# SCH_Teensy-PWM-Machine_2025-12-31.net
KiCad netlist of a schematic drawn in EasyEDA
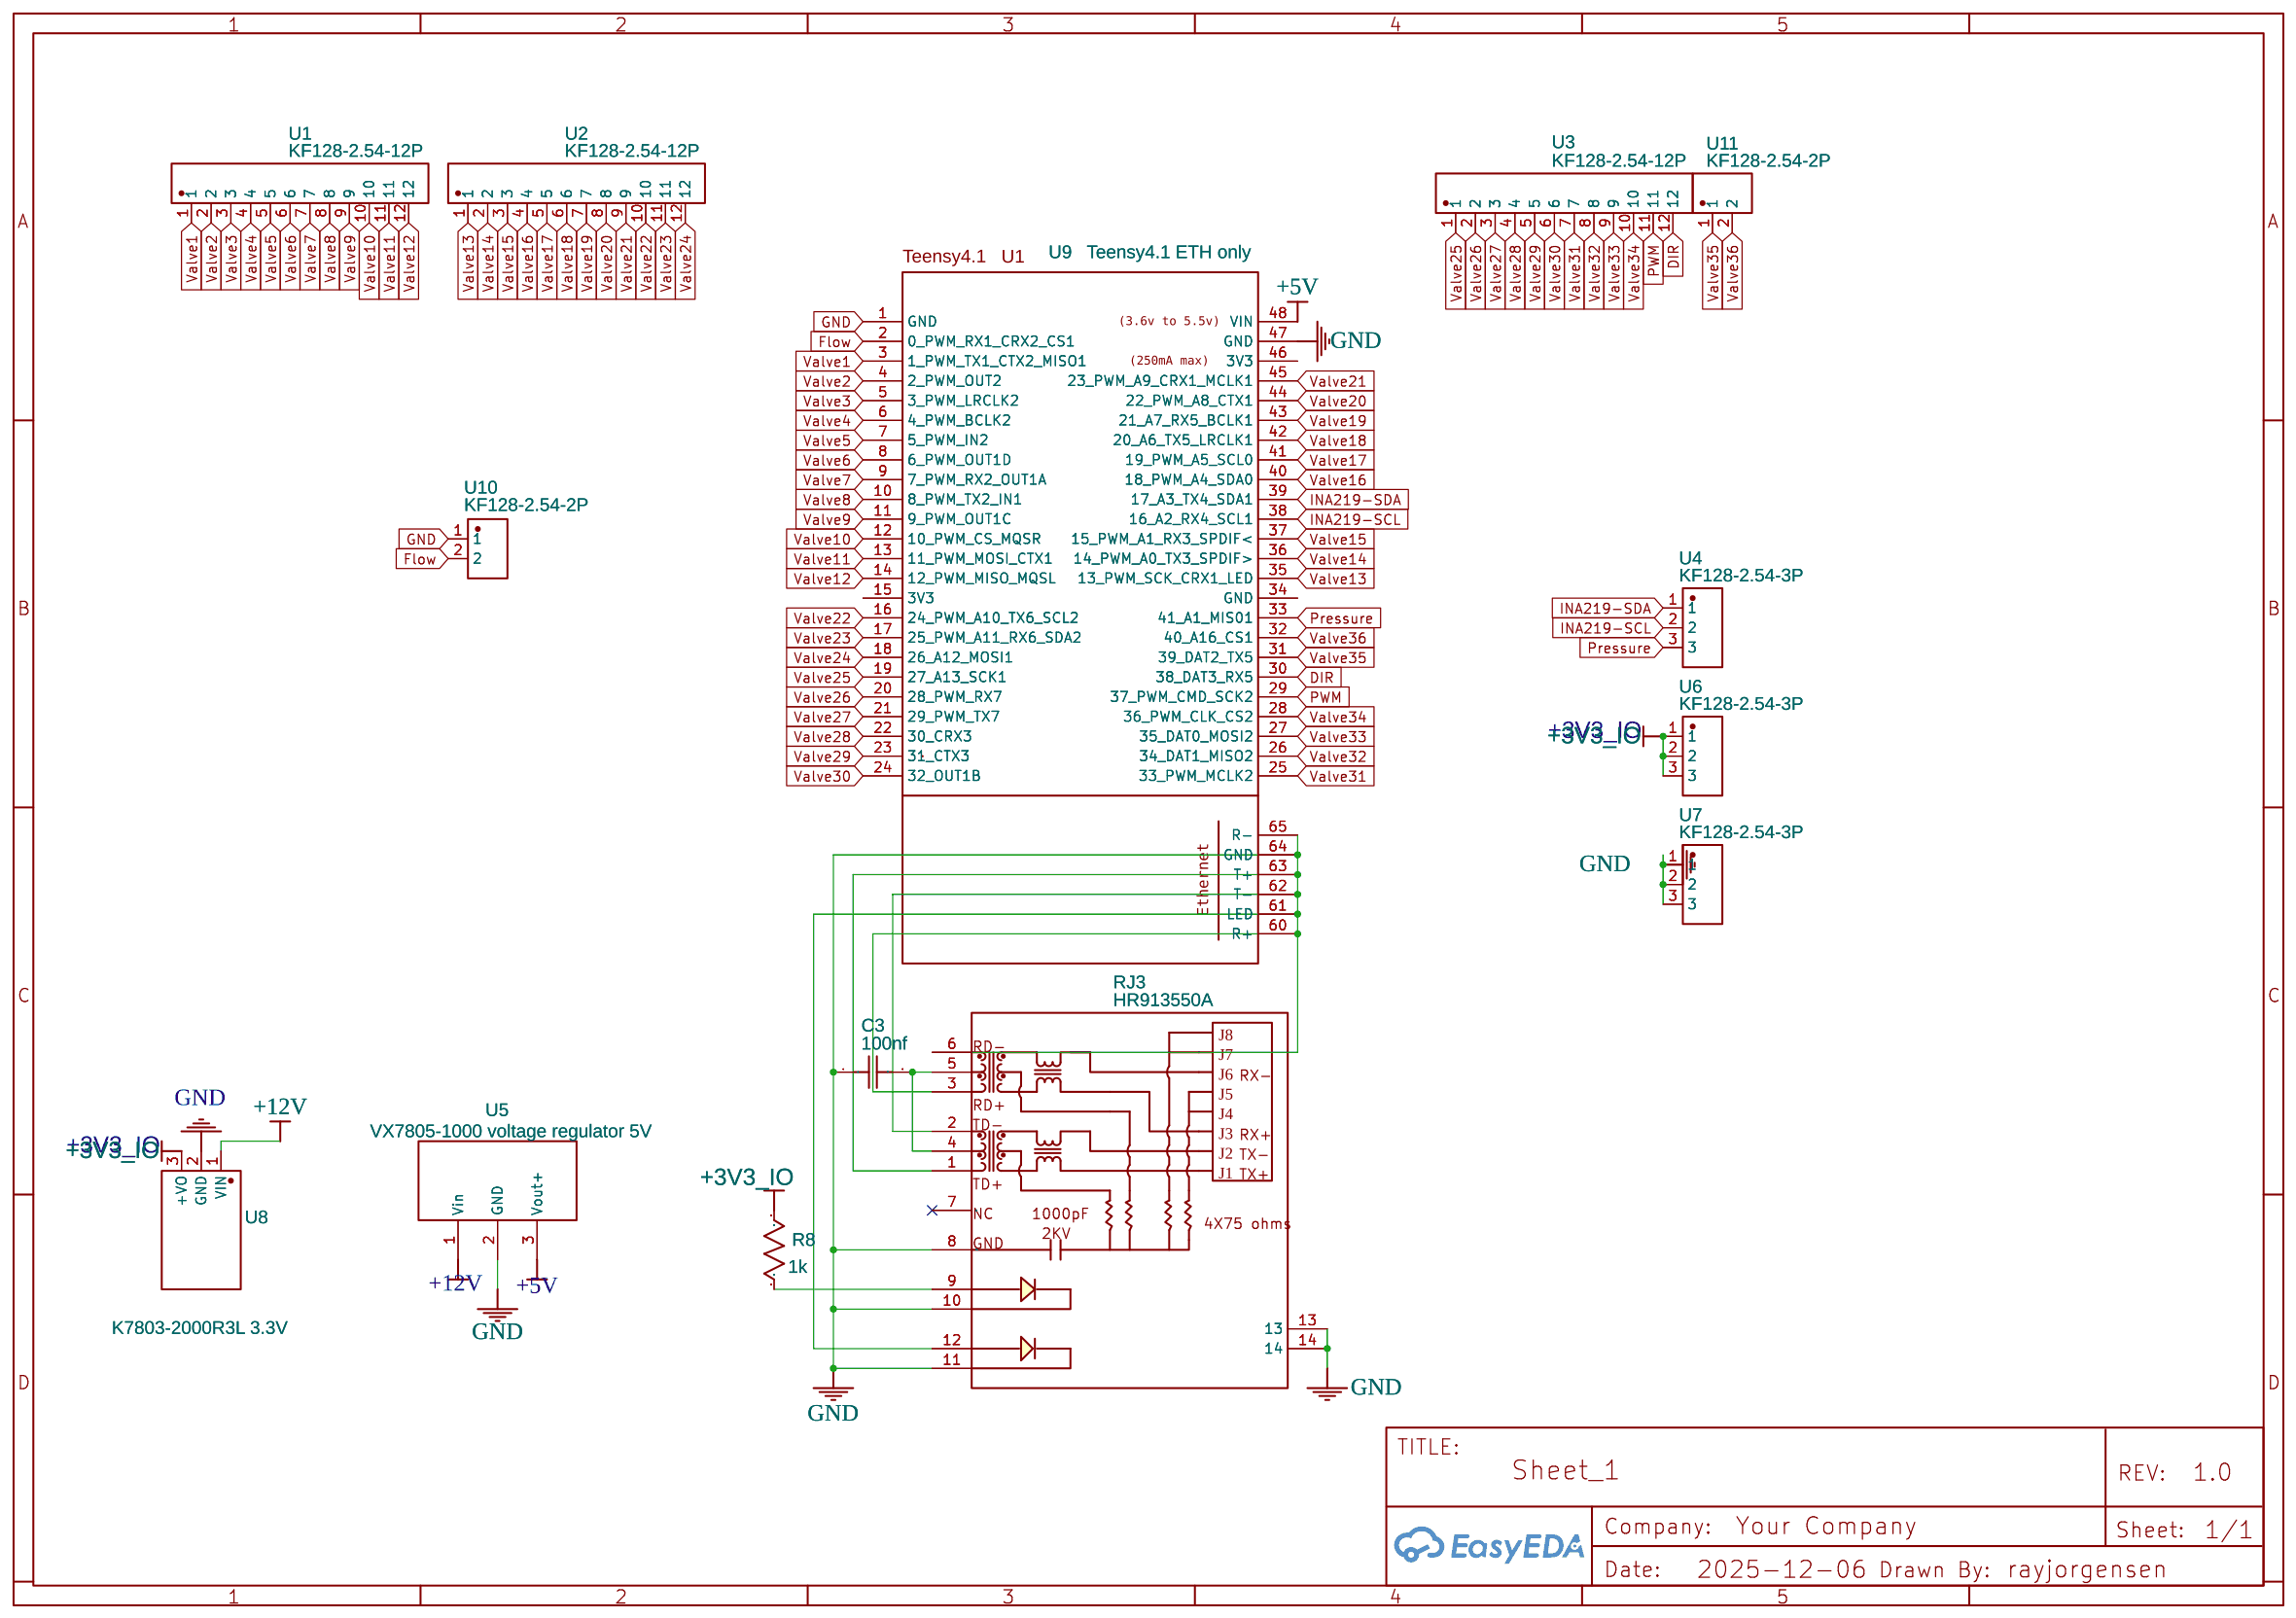
[diagram p0: schematic sheet]

(export (version "E")
  (design (tool "Eeschema 10.0.6"))
  (components
    (comp (ref "C3") (value "100nf") (libsource (lib "") (part "C_RAD-0.1_US")))
    (comp (ref "R8") (value "1k") (libsource (lib "") (part "R_AXIAL-0.4_US")))
    (comp (ref "RJ3")
      (value "HR913550A")
      (fields (field (name "Manufacturer") "HANRUN"))
      (libsource (lib "") (part "HR913550A"))
    )
    (comp (ref "U1")
      (value "KF128-2.54-12P")
      (fields (field (name "Manufacturer") "KEFA(科发)"))
      (libsource (lib "") (part "KF128-2.54-12P"))
    )
    (comp (ref "U2")
      (value "KF128-2.54-12P")
      (fields (field (name "Manufacturer") "KEFA(科发)"))
      (libsource (lib "") (part "KF128-2.54-12P"))
    )
    (comp (ref "U3")
      (value "KF128-2.54-12P")
      (fields (field (name "Manufacturer") "KEFA(科发)"))
      (libsource (lib "") (part "KF128-2.54-12P"))
    )
    (comp (ref "U4")
      (value "KF128-2.54-3P")
      (fields (field (name "Manufacturer") "KEFA(科发)"))
      (libsource (lib "") (part "KF128-2.54-3P"))
    )
    (comp (ref "U5")
      (value "VX7805-1000 voltage regulator 5V")
      (fields (field (name "Manufacturer Part") "VX7805-1000") (field (name "Manufacturer") "CUI"))
      (libsource (lib "") (part "VX7805-1000 voltage regulator"))
    )
    (comp (ref "U6")
      (value "KF128-2.54-3P")
      (fields (field (name "Manufacturer") "KEFA(科发)"))
      (libsource (lib "") (part "KF128-2.54-3P"))
    )
    (comp (ref "U7")
      (value "KF128-2.54-3P")
      (fields (field (name "Manufacturer") "KEFA(科发)"))
      (libsource (lib "") (part "KF128-2.54-3P"))
    )
    (comp (ref "U8")
      (value "K7803-2000R3L 3.3V")
      (fields
        (field (name "Manufacturer Part") "K7803-2000")
        (field (name "Manufacturer") "MORNSUN Guangzhou S& T")
      )
      (libsource (lib "") (part "K7803-2000R3L"))
    )
    (comp (ref "U9")
      (value "Teensy4.1 ETH only")
      (fields (field (name "Manufacturer Part") "Teensy4.1") (field (name "Manufacturer") "PJRC"))
      (libsource (lib "") (part "Teensy4.1 ETH only"))
    )
    (comp (ref "U10")
      (value "KF128-2.54-2P")
      (fields (field (name "Manufacturer") "KEFA(科发)"))
      (libsource (lib "") (part "KF128-2.54-2P_1"))
    )
    (comp (ref "U11")
      (value "KF128-2.54-2P")
      (fields (field (name "Manufacturer") "KEFA(科发)"))
      (libsource (lib "") (part "KF128-2.54-2P"))
    )
  )
  (nets
    (net (code "1") (name "+3V3_IO") (class "Default")
      (node (ref "R8") (pin "2") (pinfunction "2_2") (pintype "unspecified"))
      (node (ref "U6") (pin "1") (pinfunction "1_1") (pintype "unspecified"))
      (node (ref "U6") (pin "2") (pinfunction "2_2") (pintype "unspecified"))
      (node (ref "U6") (pin "3") (pinfunction "3_3") (pintype "unspecified"))
      (node (ref "U8") (pin "3") (pinfunction "+VO_3") (pintype "unspecified"))
    )
    (net (code "2") (name "+5V") (class "Default")
      (node (ref "U5") (pin "3") (pinfunction "Vout+_3") (pintype "unspecified"))
      (node (ref "U9") (pin "48") (pinfunction "VIN_48") (pintype "bidirectional"))
    )
    (net (code "3") (name "+12V") (class "Default")
      (node (ref "U5") (pin "1") (pinfunction "Vin_1") (pintype "unspecified"))
      (node (ref "U8") (pin "1") (pinfunction "VIN_1") (pintype "unspecified"))
    )
    (net (code "4") (name "DIR") (class "Default")
      (node (ref "U3") (pin "12") (pinfunction "12_12") (pintype "unspecified"))
      (node (ref "U9") (pin "30") (pinfunction "38_DAT3_RX5_30") (pintype "bidirectional"))
    )
    (net (code "5") (name "Flow") (class "Default")
      (node (ref "U10") (pin "2") (pinfunction "2_2") (pintype "unspecified"))
      (node (ref "U9") (pin "2") (pinfunction "0_PWM_RX1_CRX2_CS1_2") (pintype "bidirectional"))
    )
    (net (code "6") (name "GND") (class "Default")
      (node (ref "C3") (pin "1") (pinfunction "1_1") (pintype "unspecified"))
      (node (ref "RJ3") (pin "1") (pintype "unspecified"))
      (node (ref "RJ3") (pin "10") (pintype "unspecified"))
      (node (ref "RJ3") (pin "11") (pintype "unspecified"))
      (node (ref "RJ3") (pin "12") (pintype "unspecified"))
      (node (ref "RJ3") (pin "13") (pinfunction "13_13") (pintype "unspecified"))
      (node (ref "RJ3") (pin "14") (pinfunction "14_14") (pintype "unspecified"))
      (node (ref "RJ3") (pin "2") (pintype "unspecified"))
      (node (ref "RJ3") (pin "3") (pintype "unspecified"))
      (node (ref "RJ3") (pin "6") (pintype "unspecified"))
      (node (ref "RJ3") (pin "8") (pinfunction "GND_8") (pintype "unspecified"))
      (node (ref "U10") (pin "1") (pinfunction "1_1") (pintype "unspecified"))
      (node (ref "U5") (pin "2") (pinfunction "GND_2") (pintype "unspecified"))
      (node (ref "U7") (pin "1") (pinfunction "1_1") (pintype "unspecified"))
      (node (ref "U7") (pin "2") (pinfunction "2_2") (pintype "unspecified"))
      (node (ref "U7") (pin "3") (pinfunction "3_3") (pintype "unspecified"))
      (node (ref "U8") (pin "2") (pinfunction "GND_2") (pintype "unspecified"))
      (node (ref "U9") (pin "1") (pinfunction "GND_1") (pintype "bidirectional"))
      (node (ref "U9") (pin "47") (pinfunction "GND_47") (pintype "bidirectional"))
      (node (ref "U9") (pin "60") (pinfunction "R+_60") (pintype "bidirectional"))
      (node (ref "U9") (pin "61") (pinfunction "LED_61") (pintype "bidirectional"))
      (node (ref "U9") (pin "62") (pinfunction "T-_62") (pintype "bidirectional"))
      (node (ref "U9") (pin "63") (pinfunction "T+_63") (pintype "bidirectional"))
      (node (ref "U9") (pin "64") (pinfunction "GND_64") (pintype "bidirectional"))
      (node (ref "U9") (pin "65") (pinfunction "R-_65") (pintype "bidirectional"))
    )
    (net (code "7") (name "INA219-SCL") (class "Default")
      (node (ref "U4") (pin "2") (pinfunction "2_2") (pintype "unspecified"))
      (node (ref "U9") (pin "38") (pinfunction "16_A2_RX4_SCL1_38") (pintype "bidirectional"))
    )
    (net (code "8") (name "INA219-SDA") (class "Default")
      (node (ref "U4") (pin "1") (pinfunction "1_1") (pintype "unspecified"))
      (node (ref "U9") (pin "39") (pinfunction "17_A3_TX4_SDA1_39") (pintype "bidirectional"))
    )
    (net (code "9") (name "Net-(C3-Pad2)") (class "Default")
      (node (ref "C3") (pin "2") (pinfunction "2_2") (pintype "unspecified"))
      (node (ref "RJ3") (pin "4") (pintype "unspecified"))
      (node (ref "RJ3") (pin "5") (pintype "unspecified"))
    )
    (net (code "10") (name "Net-(R8-Pad1)") (class "Default")
      (node (ref "R8") (pin "1") (pinfunction "1_1") (pintype "unspecified"))
      (node (ref "RJ3") (pin "9") (pintype "unspecified"))
    )
    (net (code "11") (name "PWM") (class "Default")
      (node (ref "U3") (pin "11") (pinfunction "11_11") (pintype "unspecified"))
      (node (ref "U9") (pin "29") (pinfunction "37_PWM_CMD_SCK2_29") (pintype "bidirectional"))
    )
    (net (code "12") (name "Pressure") (class "Default")
      (node (ref "U4") (pin "3") (pinfunction "3_3") (pintype "unspecified"))
      (node (ref "U9") (pin "33") (pinfunction "41_A1_MIS01_33") (pintype "bidirectional"))
    )
    (net (code "13") (name "Valve1") (class "Default")
      (node (ref "U1") (pin "1") (pinfunction "1_1") (pintype "unspecified"))
      (node (ref "U9") (pin "3") (pinfunction "1_PWM_TX1_CTX2_MISO1_3") (pintype "bidirectional"))
    )
    (net (code "14") (name "Valve2") (class "Default")
      (node (ref "U1") (pin "2") (pinfunction "2_2") (pintype "unspecified"))
      (node (ref "U9") (pin "4") (pinfunction "2_PWM_OUT2_4") (pintype "bidirectional"))
    )
    (net (code "15") (name "Valve3") (class "Default")
      (node (ref "U1") (pin "3") (pinfunction "3_3") (pintype "unspecified"))
      (node (ref "U9") (pin "5") (pinfunction "3_PWM_LRCLK2_5") (pintype "bidirectional"))
    )
    (net (code "16") (name "Valve4") (class "Default")
      (node (ref "U1") (pin "4") (pinfunction "4_4") (pintype "unspecified"))
      (node (ref "U9") (pin "6") (pinfunction "4_PWM_BCLK2_6") (pintype "bidirectional"))
    )
    (net (code "17") (name "Valve5") (class "Default")
      (node (ref "U1") (pin "5") (pinfunction "5_5") (pintype "unspecified"))
      (node (ref "U9") (pin "7") (pinfunction "5_PWM_IN2_7") (pintype "bidirectional"))
    )
    (net (code "18") (name "Valve6") (class "Default")
      (node (ref "U1") (pin "6") (pinfunction "6_6") (pintype "unspecified"))
      (node (ref "U9") (pin "8") (pinfunction "6_PWM_OUT1D_8") (pintype "bidirectional"))
    )
    (net (code "19") (name "Valve7") (class "Default")
      (node (ref "U1") (pin "7") (pinfunction "7_7") (pintype "unspecified"))
      (node (ref "U9") (pin "9") (pinfunction "7_PWM_RX2_OUT1A_9") (pintype "bidirectional"))
    )
    (net (code "20") (name "Valve8") (class "Default")
      (node (ref "U1") (pin "8") (pinfunction "8_8") (pintype "unspecified"))
      (node (ref "U9") (pin "10") (pinfunction "8_PWM_TX2_IN1_10") (pintype "bidirectional"))
    )
    (net (code "21") (name "Valve9") (class "Default")
      (node (ref "U1") (pin "9") (pinfunction "9_9") (pintype "unspecified"))
      (node (ref "U9") (pin "11") (pinfunction "9_PWM_OUT1C_11") (pintype "bidirectional"))
    )
    (net (code "22") (name "Valve10") (class "Default")
      (node (ref "U1") (pin "10") (pinfunction "10_10") (pintype "unspecified"))
      (node (ref "U9") (pin "12") (pinfunction "10_PWM_CS_MQSR_12") (pintype "bidirectional"))
    )
    (net (code "23") (name "Valve11") (class "Default")
      (node (ref "U1") (pin "11") (pinfunction "11_11") (pintype "unspecified"))
      (node (ref "U9") (pin "13") (pinfunction "11_PWM_MOSI_CTX1_13") (pintype "bidirectional"))
    )
    (net (code "24") (name "Valve12") (class "Default")
      (node (ref "U1") (pin "12") (pinfunction "12_12") (pintype "unspecified"))
      (node (ref "U9") (pin "14") (pinfunction "12_PWM_MISO_MQSL_14") (pintype "bidirectional"))
    )
    (net (code "25") (name "Valve13") (class "Default")
      (node (ref "U2") (pin "1") (pinfunction "1_1") (pintype "unspecified"))
      (node (ref "U9") (pin "35") (pinfunction "13_PWM_SCK_CRX1_LED_35") (pintype "bidirectional"))
    )
    (net (code "26") (name "Valve14") (class "Default")
      (node (ref "U2") (pin "2") (pinfunction "2_2") (pintype "unspecified"))
      (node (ref "U9") (pin "36") (pinfunction "14_PWM_A0_TX3_SPDIF>_36") (pintype "bidirectional"))
    )
    (net (code "27") (name "Valve15") (class "Default")
      (node (ref "U2") (pin "3") (pinfunction "3_3") (pintype "unspecified"))
      (node (ref "U9") (pin "37") (pinfunction "15_PWM_A1_RX3_SPDIF<_37") (pintype "bidirectional"))
    )
    (net (code "28") (name "Valve16") (class "Default")
      (node (ref "U2") (pin "4") (pinfunction "4_4") (pintype "unspecified"))
      (node (ref "U9") (pin "40") (pinfunction "18_PWM_A4_SDA0_40") (pintype "bidirectional"))
    )
    (net (code "29") (name "Valve17") (class "Default")
      (node (ref "U2") (pin "5") (pinfunction "5_5") (pintype "unspecified"))
      (node (ref "U9") (pin "41") (pinfunction "19_PWM_A5_SCL0_41") (pintype "bidirectional"))
    )
    (net (code "30") (name "Valve18") (class "Default")
      (node (ref "U2") (pin "6") (pinfunction "6_6") (pintype "unspecified"))
      (node (ref "U9") (pin "42") (pinfunction "20_A6_TX5_LRCLK1_42") (pintype "bidirectional"))
    )
    (net (code "31") (name "Valve19") (class "Default")
      (node (ref "U2") (pin "7") (pinfunction "7_7") (pintype "unspecified"))
      (node (ref "U9") (pin "43") (pinfunction "21_A7_RX5_BCLK1_43") (pintype "bidirectional"))
    )
    (net (code "32") (name "Valve20") (class "Default")
      (node (ref "U2") (pin "8") (pinfunction "8_8") (pintype "unspecified"))
      (node (ref "U9") (pin "44") (pinfunction "22_PWM_A8_CTX1_44") (pintype "bidirectional"))
    )
    (net (code "33") (name "Valve21") (class "Default")
      (node (ref "U2") (pin "9") (pinfunction "9_9") (pintype "unspecified"))
      (node (ref "U9") (pin "45") (pinfunction "23_PWM_A9_CRX1_MCLK1_45") (pintype "bidirectional"))
    )
    (net (code "34") (name "Valve22") (class "Default")
      (node (ref "U2") (pin "10") (pinfunction "10_10") (pintype "unspecified"))
      (node (ref "U9") (pin "16") (pinfunction "24_PWM_A10_TX6_SCL2_16") (pintype "bidirectional"))
    )
    (net (code "35") (name "Valve23") (class "Default")
      (node (ref "U2") (pin "11") (pinfunction "11_11") (pintype "unspecified"))
      (node (ref "U9") (pin "17") (pinfunction "25_PWM_A11_RX6_SDA2_17") (pintype "bidirectional"))
    )
    (net (code "36") (name "Valve24") (class "Default")
      (node (ref "U2") (pin "12") (pinfunction "12_12") (pintype "unspecified"))
      (node (ref "U9") (pin "18") (pinfunction "26_A12_MOSI1_18") (pintype "bidirectional"))
    )
    (net (code "37") (name "Valve25") (class "Default")
      (node (ref "U3") (pin "1") (pinfunction "1_1") (pintype "unspecified"))
      (node (ref "U9") (pin "19") (pinfunction "27_A13_SCK1_19") (pintype "bidirectional"))
    )
    (net (code "38") (name "Valve26") (class "Default")
      (node (ref "U3") (pin "2") (pinfunction "2_2") (pintype "unspecified"))
      (node (ref "U9") (pin "20") (pinfunction "28_PWM_RX7_20") (pintype "bidirectional"))
    )
    (net (code "39") (name "Valve27") (class "Default")
      (node (ref "U3") (pin "3") (pinfunction "3_3") (pintype "unspecified"))
      (node (ref "U9") (pin "21") (pinfunction "29_PWM_TX7_21") (pintype "bidirectional"))
    )
    (net (code "40") (name "Valve28") (class "Default")
      (node (ref "U3") (pin "4") (pinfunction "4_4") (pintype "unspecified"))
      (node (ref "U9") (pin "22") (pinfunction "30_CRX3_22") (pintype "bidirectional"))
    )
    (net (code "41") (name "Valve29") (class "Default")
      (node (ref "U3") (pin "5") (pinfunction "5_5") (pintype "unspecified"))
      (node (ref "U9") (pin "23") (pinfunction "31_CTX3_23") (pintype "bidirectional"))
    )
    (net (code "42") (name "Valve30") (class "Default")
      (node (ref "U3") (pin "6") (pinfunction "6_6") (pintype "unspecified"))
      (node (ref "U9") (pin "24") (pinfunction "32_OUT1B_24") (pintype "bidirectional"))
    )
    (net (code "43") (name "Valve31") (class "Default")
      (node (ref "U3") (pin "7") (pinfunction "7_7") (pintype "unspecified"))
      (node (ref "U9") (pin "25") (pinfunction "33_PWM_MCLK2_25") (pintype "bidirectional"))
    )
    (net (code "44") (name "Valve32") (class "Default")
      (node (ref "U3") (pin "8") (pinfunction "8_8") (pintype "unspecified"))
      (node (ref "U9") (pin "26") (pinfunction "34_DAT1_MISO2_26") (pintype "bidirectional"))
    )
    (net (code "45") (name "Valve33") (class "Default")
      (node (ref "U3") (pin "9") (pinfunction "9_9") (pintype "unspecified"))
      (node (ref "U9") (pin "27") (pinfunction "35_DAT0_MOSI2_27") (pintype "bidirectional"))
    )
    (net (code "46") (name "Valve34") (class "Default")
      (node (ref "U3") (pin "10") (pinfunction "10_10") (pintype "unspecified"))
      (node (ref "U9") (pin "28") (pinfunction "36_PWM_CLK_CS2_28") (pintype "bidirectional"))
    )
    (net (code "47") (name "Valve35") (class "Default")
      (node (ref "U11") (pin "1") (pinfunction "1_1") (pintype "unspecified"))
      (node (ref "U9") (pin "31") (pinfunction "39_DAT2_TX5_31") (pintype "bidirectional"))
    )
    (net (code "48") (name "Valve36") (class "Default")
      (node (ref "U11") (pin "2") (pinfunction "2_2") (pintype "unspecified"))
      (node (ref "U9") (pin "32") (pinfunction "40_A16_CS1_32") (pintype "bidirectional"))
    )
    (net (code "49") (name "unconnected-(RJ3-NC-Pad7)") (class "Default")
      (node (ref "RJ3") (pin "7") (pinfunction "NC_7") (pintype "unspecified+no_connect"))
    )
    (net (code "50") (name "unconnected-(U9-3V3-Pad15)") (class "Default")
      (node (ref "U9") (pin "15") (pinfunction "3V3_15") (pintype "bidirectional"))
    )
    (net (code "51") (name "unconnected-(U9-3V3-Pad46)") (class "Default")
      (node (ref "U9") (pin "46") (pinfunction "3V3_46") (pintype "bidirectional"))
    )
    (net (code "52") (name "unconnected-(U9-GND-Pad34)") (class "Default")
      (node (ref "U9") (pin "34") (pinfunction "GND_34") (pintype "bidirectional"))
    )
  )
)
